# Modular_BO.net
KiCad netlist of a schematic drawn in Altium Designer
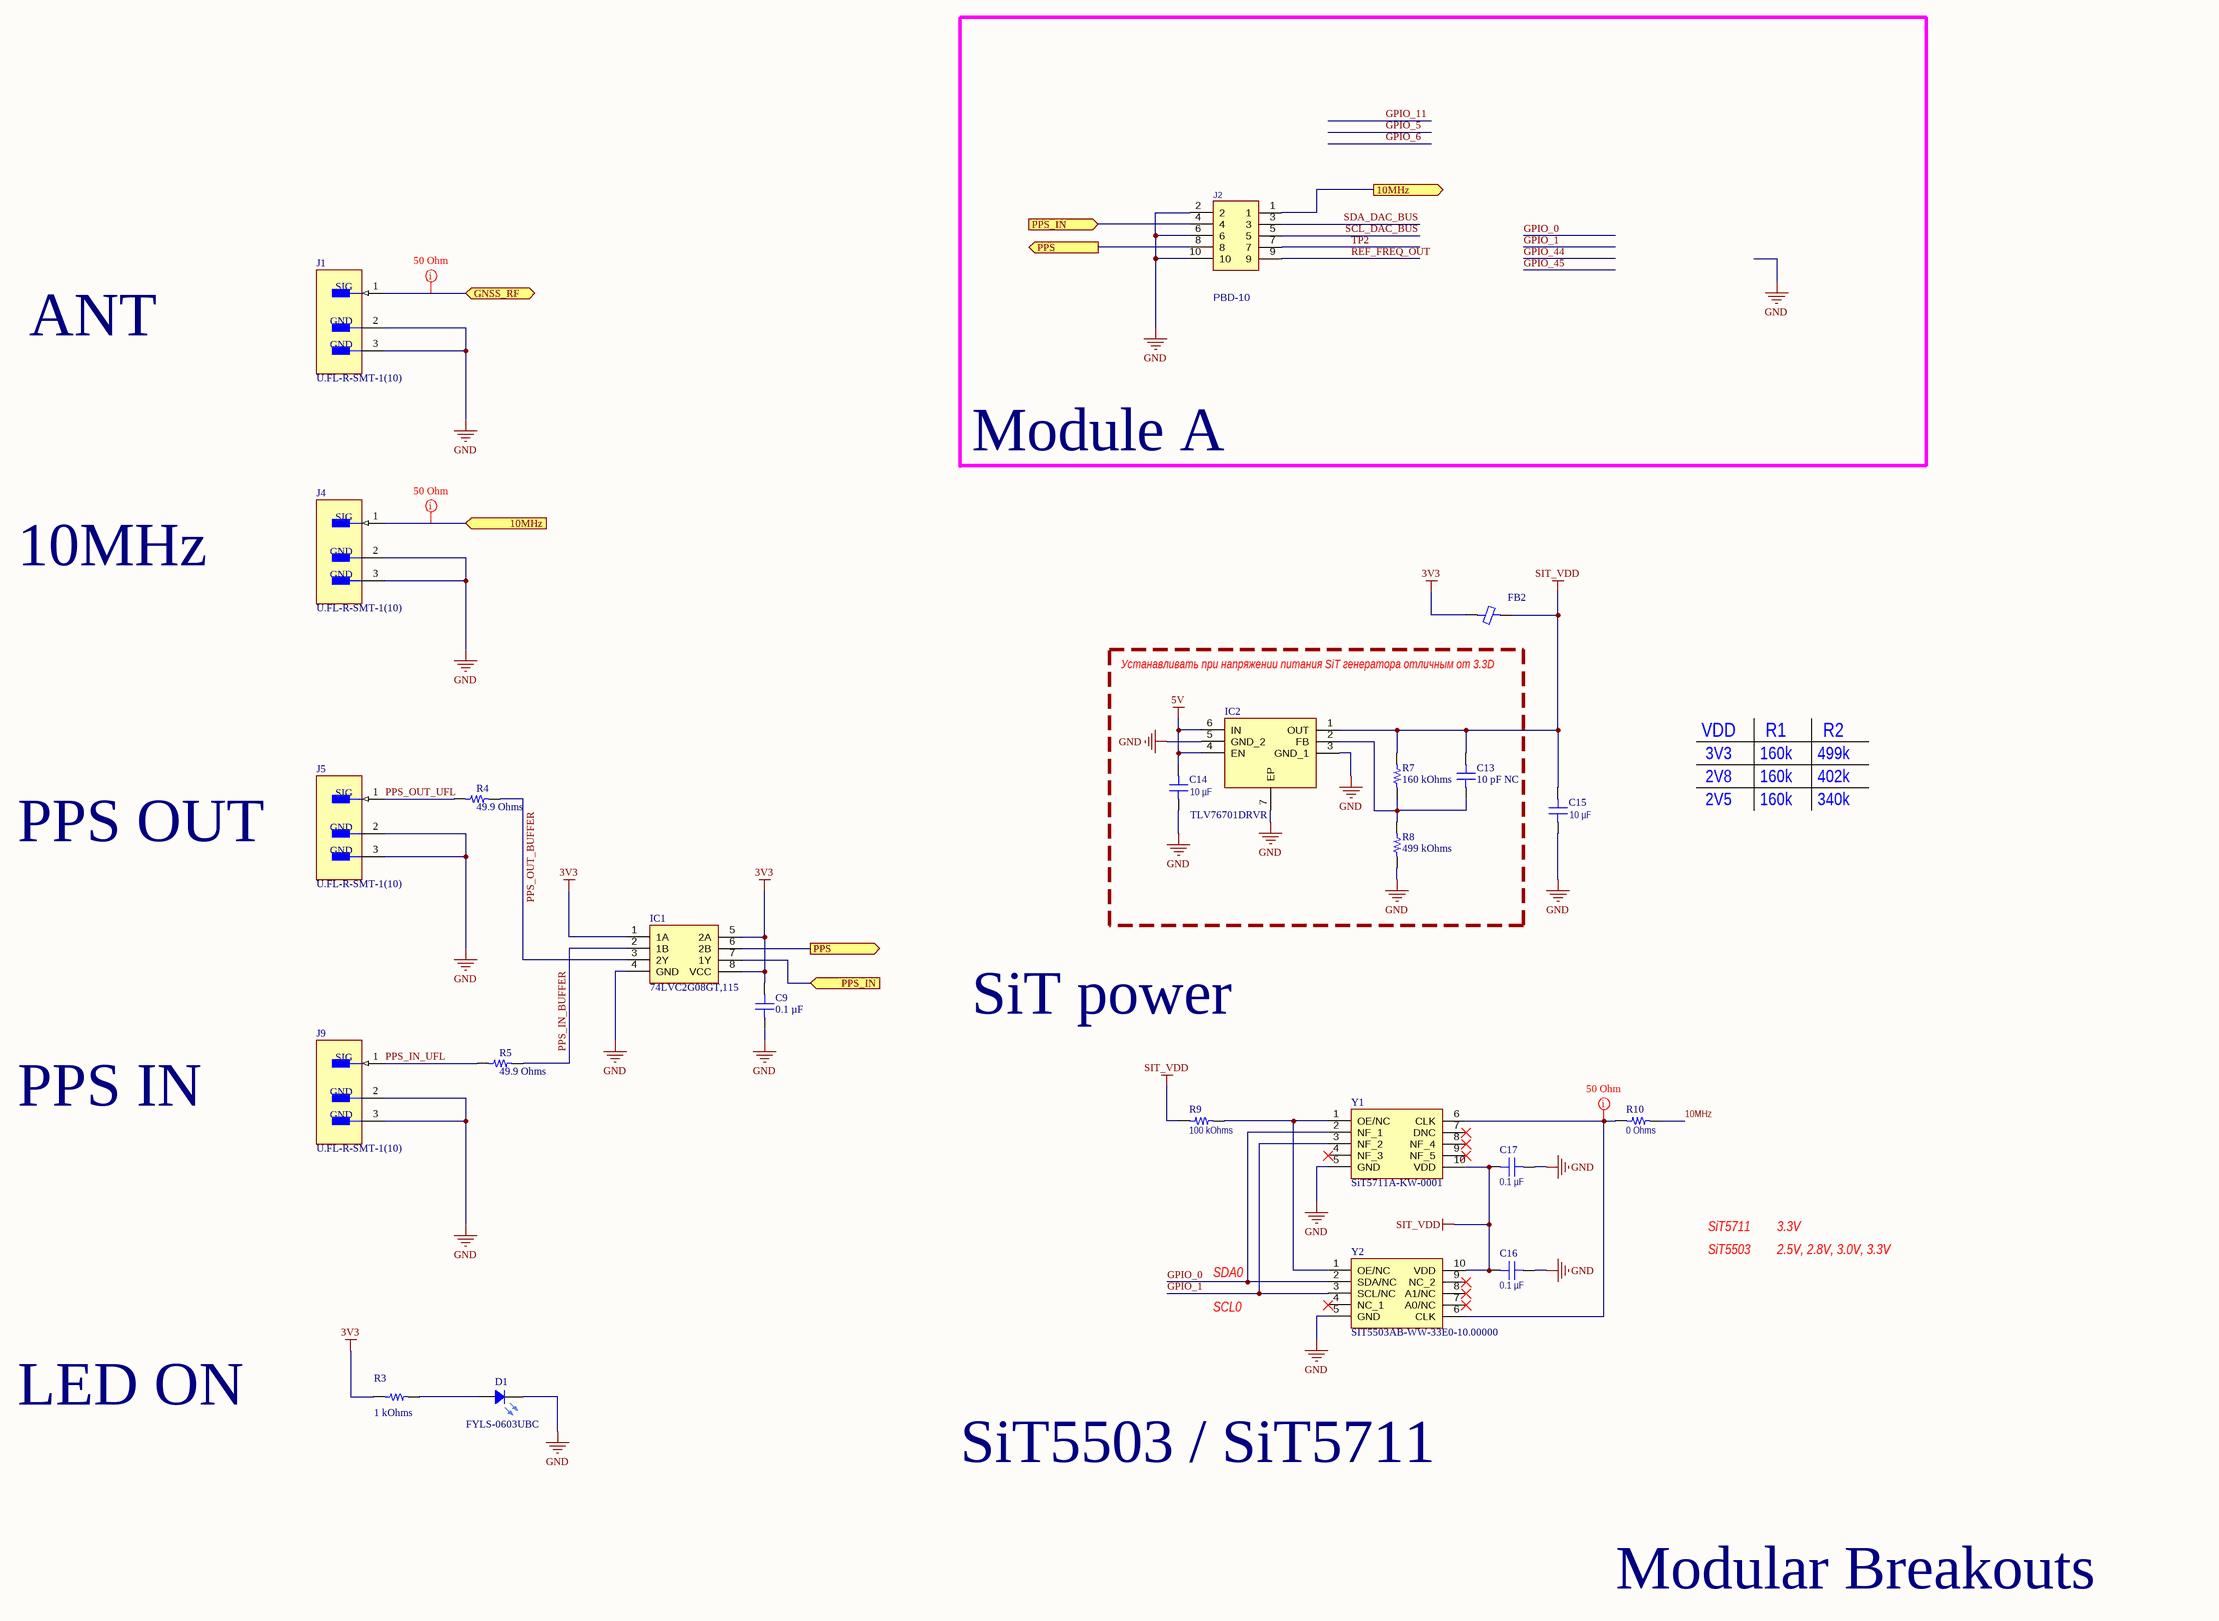
[diagram p0: Modular_BO.SchDoc]

(export (version "E")
  (design (tool "Eeschema 10.0.6"))
  (components
    (comp (ref "C9")
      (value "0.1 µF")
      (footprint "CAP 0603_1608")
      (description "CAP CER 0.1UF 50V X7R 0603")
      (fields (field (name "MANUFACTURER") "Yageo") (field (name "TOLERANCE") "±10%"))
      (libsource (lib "Celestial Altium Library - altium_library") (part "Capacitor"))
    )
    (comp (ref "C13")
      (value "10 pF NC")
      (footprint "CAP 0402_1005")
      (description "CAP CER 10PF 50V C0G/NPO 0402")
      (fields (field (name "PART NUMBER") "CC0402KRNPO9BN100") (field (name "MANUFACTURER") "Yageo"))
      (libsource (lib "Celestial Altium Library - altium_library") (part "Capacitor"))
    )
    (comp (ref "C14")
      (value "CC0603MRX5R6BB106")
      (footprint "CAP 0603_1608")
      (description "CAP CER 10UF 10V X5R 0603")
      (fields
        (field (name "CAPACITANCE") "10 µF")
        (field (name "MANUFACTURER") "Yageo")
        (field (name "TOLERANCE") "±20%")
      )
      (libsource (lib "Celestial Altium Library - altium_library") (part "Capacitor"))
    )
    (comp (ref "C15")
      (value "CC0603MRX5R6BB106")
      (footprint "CAP 0603_1608")
      (description "CAP CER 10UF 10V X5R 0603")
      (fields
        (field (name "CAPACITANCE") "10 µF")
        (field (name "MANUFACTURER") "Yageo")
        (field (name "TOLERANCE") "±20%")
      )
      (libsource (lib "Celestial Altium Library - altium_library") (part "Capacitor"))
    )
    (comp (ref "C16")
      (value "0.1 µF")
      (footprint "CAP 0603_1608")
      (description "CAP CER 0.1UF 50V X7R 0603")
      (fields (field (name "PART NUMBER") "CC0603KRX7R9BB104") (field (name "MANUFACTURER") "Yageo"))
      (libsource (lib "Celestial Altium Library - altium_library") (part "Capacitor"))
    )
    (comp (ref "C17")
      (value "0.1 µF")
      (footprint "CAP 0603_1608")
      (description "CAP CER 0.1UF 50V X7R 0603")
      (fields (field (name "PART NUMBER") "CC0603KRX7R9BB104") (field (name "MANUFACTURER") "Yageo"))
      (libsource (lib "Celestial Altium Library - altium_library") (part "Capacitor"))
    )
    (comp (ref "D1")
      (value "FYLS-0603UBC")
      (footprint "SamacSys:LEDC1608X55N_BLUE")
      (description "LED, 0603, BLUE")
      (libsource (lib "SamacSys") (part "FYLS-0603UBC"))
    )
    (comp (ref "FB2")
      (value "1 kOhms @ 100 MHz")
      (footprint "FER 0603_1608")
      (description "FERRITE BEAD 1K OHM 0603 1LN")
      (fields
        (field (name "PART NUMBER") "BLM18HG102SH1D")
        (field (name "MANUFACTURER") "Murata Electronics")
      )
      (libsource (lib "Celestial Altium Library - altium_library") (part "Ferrite Chip"))
    )
    (comp (ref "IC1")
      (value "74LVC2G08GT,115")
      (footprint "SamacSys:74AVC9112GTX")
      (description "Integrated Circuit")
      (fields (field (name "MOUSER PART NUMBER") "771-LVC2G08GT115"))
      (libsource (lib "*") (part "74LVC2G08GT,115"))
    )
    (comp (ref "IC2")
      (value "TLV76701DRVR")
      (footprint "SamacSys:SON65P200X200X80-7N")
      (description "IC REG LINEAR POS ADJ 1A 6WSON")
      (fields (field (name "MOUSER PART NUMBER") "595-TLV76701DRVR"))
      (libsource (lib "SamacSys") (part "TLV76701DRVR"))
    )
    (comp (ref "J1")
      (value "U.FL-R-SMT-1(10)")
      (footprint "FP-U_FL-R-SMT-1_10-MFG")
      (description "CONN U.FL RCPT STR 50 OHM SMD")
      (libsource (lib "Altium Content Vault") (part "7158abf7d987fa84906f6fb0d115710"))
    )
    (comp (ref "J2")
      (value "PBD-10")
      (footprint "PBD-10")
      (description "Connector")
      (fields (field (name "MANUFACTURER") "Connfly"))
      (libsource (lib "SamacSys") (part "PBD-10_1"))
    )
    (comp (ref "J4")
      (value "U.FL-R-SMT-1(10)")
      (footprint "FP-U_FL-R-SMT-1_10-MFG")
      (description "CONN U.FL RCPT STR 50 OHM SMD")
      (libsource (lib "Altium Content Vault") (part "7158abf7d987fa84906f6fb0d115710"))
    )
    (comp (ref "J5")
      (value "U.FL-R-SMT-1(10)")
      (footprint "FP-U_FL-R-SMT-1_10-MFG")
      (description "CONN U.FL RCPT STR 50 OHM SMD")
      (libsource (lib "Altium Content Vault") (part "7158abf7d987fa84906f6fb0d115710"))
    )
    (comp (ref "J9")
      (value "U.FL-R-SMT-1(10)")
      (footprint "FP-U_FL-R-SMT-1_10-MFG")
      (description "CONN U.FL RCPT STR 50 OHM SMD")
      (libsource (lib "Altium Content Vault") (part "7158abf7d987fa84906f6fb0d115710"))
    )
    (comp (ref "R3")
      (value "1 kOhms")
      (footprint "YAGEO RES 0603_1608")
      (description "RES 1K OHM 1% 1/10W 0603")
      (fields (field (name "PART NUMBER") "RC0603FR-071KL") (field (name "MANUFACTURER") "Yageo"))
      (libsource (lib "Celestial Altium Library - altium_library") (part "Resistor"))
    )
    (comp (ref "R4")
      (value "49.9 Ohms")
      (footprint "YAGEO RES 0603_1608")
      (description "RES 49.9 OHM 1% 1/10W 0603")
      (fields (field (name "PART NUMBER") "RC0603FR-0749R9L") (field (name "MANUFACTURER") "Yageo"))
      (libsource (lib "Celestial Altium Library - altium_library") (part "Resistor"))
    )
    (comp (ref "R5")
      (value "49.9 Ohms")
      (footprint "YAGEO RES 0603_1608")
      (description "RES 49.9 OHM 1% 1/10W 0603")
      (fields (field (name "PART NUMBER") "RC0603FR-0749R9L") (field (name "MANUFACTURER") "Yageo"))
      (libsource (lib "Celestial Altium Library - altium_library") (part "Resistor"))
    )
    (comp (ref "R7")
      (value "160 kOhms")
      (footprint "YAGEO RES 0402_1005")
      (description "RES 160K OHM 1% 1/16W 0402")
      (fields (field (name "PART NUMBER") "RC0402FR-07160KL") (field (name "MANUFACTURER") "Yageo"))
      (libsource (lib "Celestial Altium Library - altium_library") (part "Resistor"))
    )
    (comp (ref "R8")
      (value "499 kOhms")
      (footprint "YAGEO RES 0402_1005")
      (description "RES 499K OHM 1% 1/16W 0402")
      (fields (field (name "PART NUMBER") "RC0402FR-07499KL") (field (name "MANUFACTURER") "Yageo"))
      (libsource (lib "Celestial Altium Library - altium_library") (part "Resistor"))
    )
    (comp (ref "R9")
      (value "100 kOhms")
      (footprint "YAGEO RES 0603_1608")
      (description "RES 100K OHM 1% 1/10W 0603")
      (fields (field (name "PART NUMBER") "RC0603FR-07100KL") (field (name "MANUFACTURER") "Yageo"))
      (libsource (lib "Celestial Altium Library - altium_library") (part "Resistor"))
    )
    (comp (ref "R10")
      (value "0 Ohms")
      (footprint "YAGEO RES 0603_1608")
      (description "RES 0 OHM JUMPER 1/10W 0603")
      (fields (field (name "PART NUMBER") "RC0603FR-070RL") (field (name "MANUFACTURER") "Yageo"))
      (libsource (lib "Celestial Altium Library - altium_library") (part "Resistor"))
    )
    (comp (ref "Y1")
      (value "SiT5711A-KW-0001")
      (footprint "SamacSys:Emerald_9070_10pins_2022")
      (description "Crystal or Oscillator")
      (libsource (lib "SamacSys") (part "SiT5711A-KW-0001"))
    )
    (comp (ref "Y2")
      (value "SIT5503AB-WW-33E0-10.00000")
      (footprint "SamacSys:Ceramic_QFN_7050_10pins")
      (description "Crystal or Oscillator")
      (libsource (lib "SamacSys") (part "SIT5503AB-WW-33E0-10.00000"))
    )
  )
  (nets
    (net (code "1") (name "/10MHz") (class "Default")
      (node (ref "J2") (pin "1") (pinfunction "1_1") (pintype "passive"))
      (node (ref "J4") (pin "1") (pinfunction "SIG_1") (pintype "input"))
      (node (ref "R10") (pin "1") (pinfunction "1_1") (pintype "passive"))
    )
    (net (code "2") (name "/GNSS_RF") (class "Default")
      (node (ref "J1") (pin "1") (pinfunction "SIG_1") (pintype "input"))
    )
    (net (code "3") (name "/GPIO_0") (class "Default")
      (node (ref "Y1") (pin "2") (pinfunction "NF_1_2") (pintype "passive"))
      (node (ref "Y2") (pin "2") (pinfunction "SDA/NC_2") (pintype "passive"))
    )
    (net (code "4") (name "/GPIO_1") (class "Default")
      (node (ref "Y1") (pin "3") (pinfunction "NF_2_3") (pintype "passive"))
      (node (ref "Y2") (pin "3") (pinfunction "SCL/NC_3") (pintype "passive"))
    )
    (net (code "10") (name "/PPS") (class "Default")
      (node (ref "IC1") (pin "6") (pinfunction "2B_6") (pintype "passive"))
      (node (ref "J2") (pin "8") (pinfunction "8_8") (pintype "passive"))
    )
    (net (code "11") (name "/PPS_IN") (class "Default")
      (node (ref "IC1") (pin "7") (pinfunction "1Y_7") (pintype "passive"))
      (node (ref "J2") (pin "4") (pinfunction "4_4") (pintype "passive"))
    )
    (net (code "12") (name "/PPS_IN_BUFFER") (class "Default")
      (node (ref "IC1") (pin "2") (pinfunction "1B_2") (pintype "passive"))
      (node (ref "R5") (pin "2") (pinfunction "2_2") (pintype "passive"))
    )
    (net (code "13") (name "/PPS_IN_UFL") (class "Default")
      (node (ref "J9") (pin "1") (pinfunction "SIG_1") (pintype "input"))
      (node (ref "R5") (pin "1") (pinfunction "1_1") (pintype "passive"))
    )
    (net (code "14") (name "/PPS_OUT_BUFFER") (class "Default")
      (node (ref "IC1") (pin "3") (pinfunction "2Y_3") (pintype "passive"))
      (node (ref "R4") (pin "2") (pinfunction "2_2") (pintype "passive"))
    )
    (net (code "15") (name "/PPS_OUT_UFL") (class "Default")
      (node (ref "J5") (pin "1") (pinfunction "SIG_1") (pintype "input"))
      (node (ref "R4") (pin "1") (pinfunction "1_1") (pintype "passive"))
    )
    (net (code "16") (name "/REF_FREQ_OUT") (class "Default")
      (node (ref "J2") (pin "9") (pinfunction "9_9") (pintype "passive"))
    )
    (net (code "17") (name "/SCL_DAC_BUS") (class "Default")
      (node (ref "J2") (pin "5") (pinfunction "5_5") (pintype "passive"))
    )
    (net (code "18") (name "/SDA_DAC_BUS") (class "Default")
      (node (ref "J2") (pin "3") (pinfunction "3_3") (pintype "passive"))
    )
    (net (code "19") (name "/TP2") (class "Default")
      (node (ref "J2") (pin "7") (pinfunction "7_7") (pintype "passive"))
    )
    (net (code "20") (name "3V3") (class "Default")
      (node (ref "C9") (pin "2") (pinfunction "2_2") (pintype "passive"))
      (node (ref "FB2") (pin "1") (pinfunction "1_1") (pintype "passive"))
      (node (ref "IC1") (pin "1") (pinfunction "1A_1") (pintype "passive"))
      (node (ref "IC1") (pin "5") (pinfunction "2A_5") (pintype "passive"))
      (node (ref "IC1") (pin "8") (pinfunction "VCC_8") (pintype "passive"))
      (node (ref "R3") (pin "1") (pinfunction "1_1") (pintype "passive"))
    )
    (net (code "21") (name "5V") (class "Default")
      (node (ref "C14") (pin "2") (pinfunction "2_2") (pintype "passive"))
      (node (ref "IC2") (pin "4") (pinfunction "EN_4") (pintype "passive"))
      (node (ref "IC2") (pin "6") (pinfunction "IN_6") (pintype "passive"))
    )
    (net (code "22") (name "GND") (class "Default")
      (node (ref "C14") (pin "1") (pinfunction "1_1") (pintype "passive"))
      (node (ref "C15") (pin "1") (pinfunction "1_1") (pintype "passive"))
      (node (ref "C16") (pin "1") (pinfunction "1_1") (pintype "passive"))
      (node (ref "C17") (pin "1") (pinfunction "1_1") (pintype "passive"))
      (node (ref "C9") (pin "1") (pinfunction "1_1") (pintype "passive"))
      (node (ref "D1") (pin "1") (pinfunction "A_1") (pintype "passive"))
      (node (ref "IC1") (pin "4") (pinfunction "GND_4") (pintype "passive"))
      (node (ref "IC2") (pin "3") (pinfunction "GND_1_3") (pintype "passive"))
      (node (ref "IC2") (pin "5") (pinfunction "GND_2_5") (pintype "passive"))
      (node (ref "IC2") (pin "7") (pinfunction "EP_7") (pintype "passive"))
      (node (ref "J1") (pin "2") (pinfunction "GND_2") (pintype "power_in"))
      (node (ref "J1") (pin "3") (pinfunction "GND_3") (pintype "power_in"))
      (node (ref "J2") (pin "10") (pinfunction "10_10") (pintype "passive"))
      (node (ref "J2") (pin "2") (pinfunction "2_2") (pintype "passive"))
      (node (ref "J2") (pin "6") (pinfunction "6_6") (pintype "passive"))
      (node (ref "J4") (pin "2") (pinfunction "GND_2") (pintype "power_in"))
      (node (ref "J4") (pin "3") (pinfunction "GND_3") (pintype "power_in"))
      (node (ref "J5") (pin "2") (pinfunction "GND_2") (pintype "power_in"))
      (node (ref "J5") (pin "3") (pinfunction "GND_3") (pintype "power_in"))
      (node (ref "J9") (pin "2") (pinfunction "GND_2") (pintype "power_in"))
      (node (ref "J9") (pin "3") (pinfunction "GND_3") (pintype "power_in"))
      (node (ref "R8") (pin "1") (pinfunction "1_1") (pintype "passive"))
      (node (ref "Y1") (pin "5") (pinfunction "GND_5") (pintype "passive"))
      (node (ref "Y2") (pin "5") (pinfunction "GND_5") (pintype "passive"))
    )
    (net (code "23") (name "Net-(D1-C)") (class "Default")
      (node (ref "D1") (pin "2") (pinfunction "C_2") (pintype "passive"))
      (node (ref "R3") (pin "2") (pinfunction "2_2") (pintype "passive"))
    )
    (net (code "24") (name "Net-(IC2-FB)") (class "Default")
      (node (ref "C13") (pin "1") (pinfunction "1_1") (pintype "passive"))
      (node (ref "IC2") (pin "2") (pinfunction "FB_2") (pintype "passive"))
      (node (ref "R7") (pin "1") (pinfunction "1_1") (pintype "passive"))
      (node (ref "R8") (pin "2") (pinfunction "2_2") (pintype "passive"))
    )
    (net (code "25") (name "Net-(Y1-CLK)") (class "Default")
      (node (ref "R10") (pin "2") (pinfunction "2_2") (pintype "passive"))
      (node (ref "Y1") (pin "6") (pinfunction "CLK_6") (pintype "passive"))
      (node (ref "Y2") (pin "6") (pinfunction "CLK_6") (pintype "passive"))
    )
    (net (code "26") (name "Net-(Y1-OE{slash}NC)") (class "Default")
      (node (ref "R9") (pin "2") (pinfunction "2_2") (pintype "passive"))
      (node (ref "Y1") (pin "1") (pinfunction "OE/NC_1") (pintype "passive"))
      (node (ref "Y2") (pin "1") (pinfunction "OE/NC_1") (pintype "passive"))
    )
    (net (code "27") (name "SIT_VDD") (class "Default")
      (node (ref "C13") (pin "2") (pinfunction "2_2") (pintype "passive"))
      (node (ref "C15") (pin "2") (pinfunction "2_2") (pintype "passive"))
      (node (ref "C16") (pin "2") (pinfunction "2_2") (pintype "passive"))
      (node (ref "C17") (pin "2") (pinfunction "2_2") (pintype "passive"))
      (node (ref "FB2") (pin "2") (pinfunction "2_2") (pintype "passive"))
      (node (ref "IC2") (pin "1") (pinfunction "OUT_1") (pintype "passive"))
      (node (ref "R7") (pin "2") (pinfunction "2_2") (pintype "passive"))
      (node (ref "R9") (pin "1") (pinfunction "1_1") (pintype "passive"))
      (node (ref "Y1") (pin "10") (pinfunction "VDD_10") (pintype "passive"))
      (node (ref "Y2") (pin "10") (pinfunction "VDD_10") (pintype "passive"))
    )
    (net (code "28") (name "unconnected-(Y1-DNC-Pad7)") (class "Default")
      (node (ref "Y1") (pin "7") (pinfunction "DNC_7") (pintype "passive+no_connect"))
    )
    (net (code "29") (name "unconnected-(Y1-NF_3-Pad4)") (class "Default")
      (node (ref "Y1") (pin "4") (pinfunction "NF_3_4") (pintype "passive+no_connect"))
    )
    (net (code "30") (name "unconnected-(Y1-NF_4-Pad8)") (class "Default")
      (node (ref "Y1") (pin "8") (pinfunction "NF_4_8") (pintype "passive+no_connect"))
    )
    (net (code "31") (name "unconnected-(Y1-NF_5-Pad9)") (class "Default")
      (node (ref "Y1") (pin "9") (pinfunction "NF_5_9") (pintype "passive+no_connect"))
    )
    (net (code "32") (name "unconnected-(Y2-A0{slash}NC-Pad7)") (class "Default")
      (node (ref "Y2") (pin "7") (pinfunction "A0/NC_7") (pintype "passive+no_connect"))
    )
    (net (code "33") (name "unconnected-(Y2-A1{slash}NC-Pad8)") (class "Default")
      (node (ref "Y2") (pin "8") (pinfunction "A1/NC_8") (pintype "passive+no_connect"))
    )
    (net (code "34") (name "unconnected-(Y2-NC_1-Pad4)") (class "Default")
      (node (ref "Y2") (pin "4") (pinfunction "NC_1_4") (pintype "passive+no_connect"))
    )
    (net (code "35") (name "unconnected-(Y2-NC_2-Pad9)") (class "Default")
      (node (ref "Y2") (pin "9") (pinfunction "NC_2_9") (pintype "passive+no_connect"))
    )
  )
)
